# Part17_I2C_SHT30.net
KiCad netlist of a schematic drawn in Altium Designer
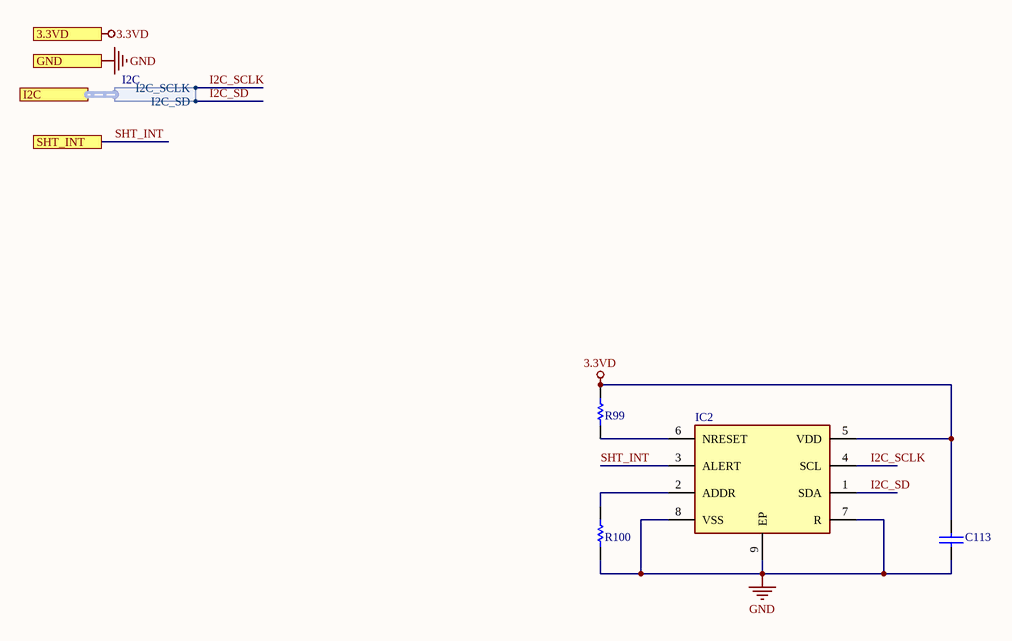
[diagram p0: Part17_I2C_SHT30.SchDoc]

(export (version "E")
  (design (tool "Eeschema 10.0.6"))
  (components
    (comp (ref "C113")
      (value "100nF")
      (footprint "0402C")
      (description "无极性电容")
      (libsource (lib "电容") (part "CAP"))
    )
    (comp (ref "IC2")
      (value "SHT31-DIS-B2.5KS")
      (footprint "SamacSys:SON50P250X250X100-9N-D")
      (description "Integrated Circuit")
      (fields (field (name "MOUSER PART NUMBER") "403-SHT31-DIS-B"))
      (libsource (lib "SamacSys") (part "SHT31-DIS-B2.5KS"))
    )
    (comp (ref "R99") (value "10K") (footprint "0402R") (libsource (lib "电阻") (part "RES")))
    (comp (ref "R100") (value "10K") (footprint "0402R") (libsource (lib "电阻") (part "RES")))
  )
  (nets
    (net (code "2") (name "/I2C_SCLK") (class "Default")
      (node (ref "IC2") (pin "4") (pinfunction "SCL_4") (pintype "passive"))
    )
    (net (code "3") (name "/I2C_SD") (class "Default")
      (node (ref "IC2") (pin "1") (pinfunction "SDA_1") (pintype "passive"))
    )
    (net (code "4") (name "/SHT_INT") (class "Default")
      (node (ref "IC2") (pin "3") (pinfunction "ALERT_3") (pintype "passive"))
    )
    (net (code "6") (name "3.3VD") (class "Default")
      (node (ref "C113") (pin "1") (pinfunction "1_1") (pintype "passive"))
      (node (ref "IC2") (pin "5") (pinfunction "VDD_5") (pintype "passive"))
      (node (ref "R99") (pin "2") (pinfunction "2_2") (pintype "passive"))
    )
    (net (code "7") (name "GND") (class "Default")
      (node (ref "C113") (pin "2") (pinfunction "2_2") (pintype "passive"))
      (node (ref "IC2") (pin "7") (pinfunction "R_7") (pintype "passive"))
      (node (ref "IC2") (pin "8") (pinfunction "VSS_8") (pintype "passive"))
      (node (ref "IC2") (pin "9") (pinfunction "EP_9") (pintype "passive"))
      (node (ref "R100") (pin "1") (pinfunction "1_1") (pintype "passive"))
    )
    (net (code "8") (name "Net-(IC2-ADDR)") (class "Default")
      (node (ref "IC2") (pin "2") (pinfunction "ADDR_2") (pintype "passive"))
      (node (ref "R100") (pin "2") (pinfunction "2_2") (pintype "passive"))
    )
    (net (code "9") (name "Net-(IC2-NRESET)") (class "Default")
      (node (ref "IC2") (pin "6") (pinfunction "NRESET_6") (pintype "passive"))
      (node (ref "R99") (pin "1") (pinfunction "1_1") (pintype "passive"))
    )
  )
)
